# GATE_DRIVE.net
KiCad netlist of a schematic drawn in Altium Designer
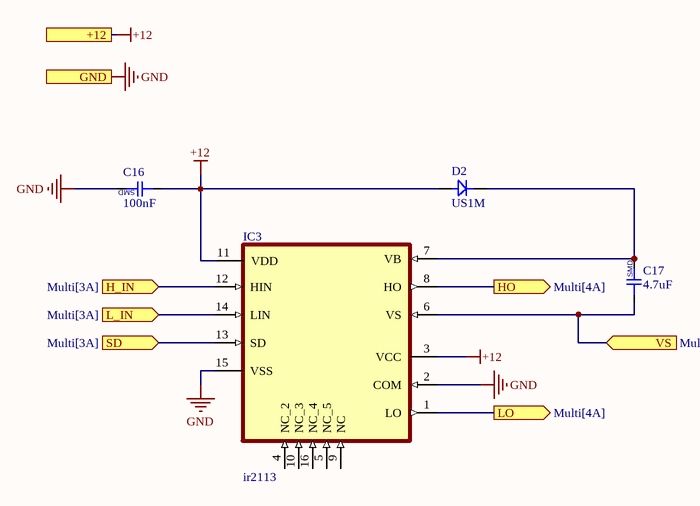
[diagram p0: GATE_DRIVE.SchDoc]

(export (version "E")
  (design (tool "Eeschema 10.0.6"))
  (components
    (comp (ref "C16")
      (value "100nF")
      (footprint "CAP-0805")
      (libsource (lib "kave-eng-pro") (part "cap_smd"))
    )
    (comp (ref "C17")
      (value "4.7uF")
      (footprint "CAP-0805")
      (libsource (lib "kave-eng-pro") (part "cap_smd"))
    )
    (comp (ref "D2")
      (value "US1M")
      (footprint "DIOD/1N4007/SMD")
      (libsource (lib "kave-eng-pro") (part "DIOD/RECTIFIERS"))
    )
    (comp (ref "IC3") (value "ir2113") (footprint "ir2113") (libsource (lib "kave-eng-pro") (part "ir2113")))
  )
  (nets
    (net (code "1") (name "+12") (class "Default")
      (node (ref "C16") (pin "1") (pintype "passive"))
      (node (ref "D2") (pin "A") (pintype "passive"))
      (node (ref "IC3") (pin "11") (pinfunction "VDD_11") (pintype "power_in"))
      (node (ref "IC3") (pin "3") (pinfunction "VCC_3") (pintype "power_in"))
    )
    (net (code "2") (name "/HO") (class "Default")
      (node (ref "IC3") (pin "8") (pinfunction "HO_8") (pintype "output"))
    )
    (net (code "3") (name "/H_IN") (class "Default")
      (node (ref "IC3") (pin "12") (pinfunction "HIN_12") (pintype "input"))
    )
    (net (code "4") (name "/LO") (class "Default")
      (node (ref "IC3") (pin "1") (pinfunction "LO_1") (pintype "output"))
    )
    (net (code "5") (name "/L_IN") (class "Default")
      (node (ref "IC3") (pin "14") (pinfunction "LIN_14") (pintype "input"))
    )
    (net (code "6") (name "/SD") (class "Default")
      (node (ref "IC3") (pin "13") (pinfunction "SD_13") (pintype "input"))
    )
    (net (code "7") (name "/VS") (class "Default")
      (node (ref "C17") (pin "1") (pintype "passive"))
      (node (ref "IC3") (pin "6") (pinfunction "VS_6") (pintype "input"))
    )
    (net (code "8") (name "GND") (class "Default")
      (node (ref "C16") (pin "2") (pintype "passive"))
      (node (ref "IC3") (pin "15") (pinfunction "VSS_15") (pintype "passive"))
      (node (ref "IC3") (pin "2") (pinfunction "COM_2") (pintype "input"))
    )
    (net (code "9") (name "Net-(IC3-VB)") (class "Default")
      (node (ref "C17") (pin "2") (pintype "passive"))
      (node (ref "D2") (pin "K") (pintype "passive"))
      (node (ref "IC3") (pin "7") (pinfunction "VB_7") (pintype "input"))
    )
    (net (code "10") (name "unconnected-(IC3-NC-Pad9)") (class "Default")
      (node (ref "IC3") (pin "9") (pinfunction "NC_9") (pintype "input"))
    )
    (net (code "11") (name "unconnected-(IC3-NC_2-Pad4)") (class "Default")
      (node (ref "IC3") (pin "4") (pinfunction "NC_2_4") (pintype "input"))
    )
    (net (code "12") (name "unconnected-(IC3-NC_3-Pad10)") (class "Default")
      (node (ref "IC3") (pin "10") (pinfunction "NC_3_10") (pintype "input"))
    )
    (net (code "13") (name "unconnected-(IC3-NC_4-Pad16)") (class "Default")
      (node (ref "IC3") (pin "16") (pinfunction "NC_4_16") (pintype "input"))
    )
    (net (code "14") (name "unconnected-(IC3-NC_5-Pad5)") (class "Default")
      (node (ref "IC3") (pin "5") (pinfunction "NC_5_5") (pintype "input"))
    )
  )
)
